# Sheet1.net
KiCad netlist of a schematic drawn in Altium Designer
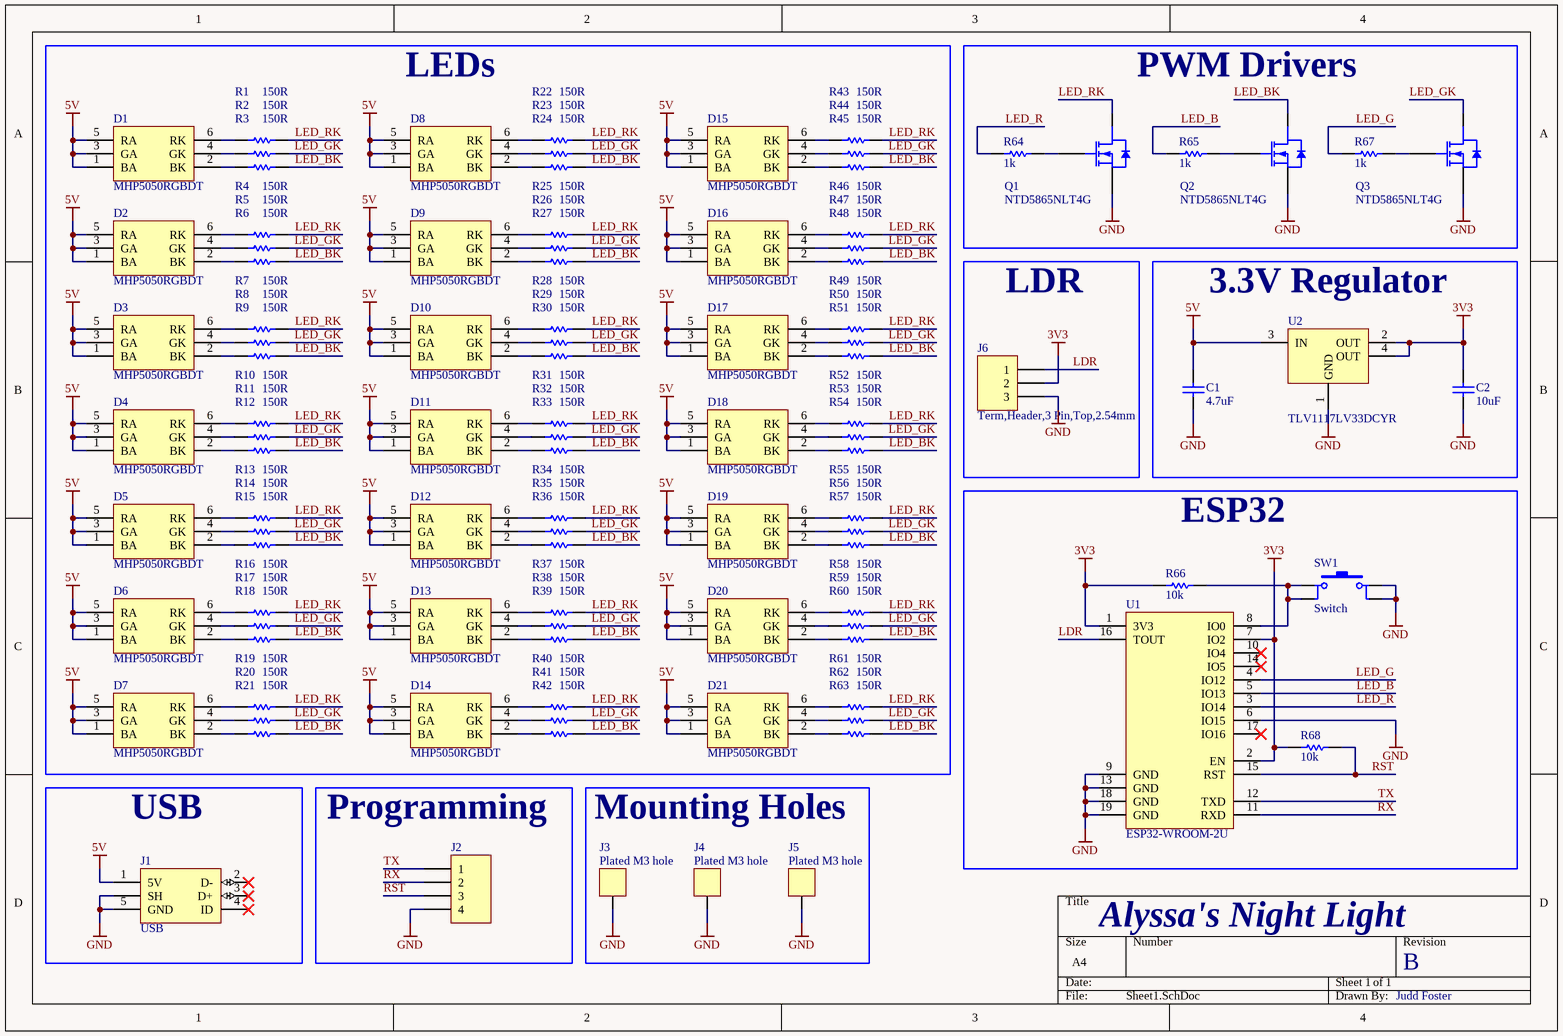
[diagram p0: Sheet1.SchDoc]

(export (version "E")
  (design (tool "Eeschema 10.0.6"))
  (components
    (comp (ref "C1")
      (value "4.7uF")
      (footprint "Cap,SMD,0805")
      (description "4.7µF ±10% 16V Ceramic Capacitor X7R 0805 (2012 Metric)")
      (fields
        (field (name "VENDOR PART NUMBER") "490-14466-1-ND")
        (field (name "MANUFACTURER") "KEMET")
        (field (name "CREATEDBY") "Judd Foster")
      )
      (libsource (lib "symbols") (part "CAP,Cer,4.7uF,16VDC,X7R,0805"))
    )
    (comp (ref "C2")
      (value "10uF")
      (footprint "Cap,SMD,0805")
      (description "CAP CER 10UF 10V X5R 0805")
      (fields
        (field (name "VENDOR PART NUMBER") "399-4925-1-ND")
        (field (name "MANUFACTURER") "KEMET")
        (field (name "CREATEDBY") "Judd Foster")
      )
      (libsource (lib "symbols") (part "CAP,Cer,10uF,10VDC,X5R,0805"))
    )
    (comp (ref "D1")
      (value "MHP5050RGBDT")
      (footprint "LED,RGB,SMD,5050")
      (description "SMD,5x5mm Light Emitting Diodes (LED) RoHS")
      (fields
        (field (name "MANUFACTURER") "MEIHUA")
        (field (name "VENDOR PART NUMBER") "C409780")
        (field (name "CREATEDBY") "Judd Foster")
      )
      (libsource (lib "symbols") (part "LED,Tri-Color,RGB,SMD,5050"))
    )
    (comp (ref "D2")
      (value "MHP5050RGBDT")
      (footprint "LED,RGB,SMD,5050")
      (description "SMD,5x5mm Light Emitting Diodes (LED) RoHS")
      (fields
        (field (name "MANUFACTURER") "MEIHUA")
        (field (name "VENDOR PART NUMBER") "C409780")
        (field (name "CREATEDBY") "Judd Foster")
      )
      (libsource (lib "symbols") (part "LED,Tri-Color,RGB,SMD,5050"))
    )
    (comp (ref "D3")
      (value "MHP5050RGBDT")
      (footprint "LED,RGB,SMD,5050")
      (description "SMD,5x5mm Light Emitting Diodes (LED) RoHS")
      (fields
        (field (name "MANUFACTURER") "MEIHUA")
        (field (name "VENDOR PART NUMBER") "C409780")
        (field (name "CREATEDBY") "Judd Foster")
      )
      (libsource (lib "symbols") (part "LED,Tri-Color,RGB,SMD,5050"))
    )
    (comp (ref "D4")
      (value "MHP5050RGBDT")
      (footprint "LED,RGB,SMD,5050")
      (description "SMD,5x5mm Light Emitting Diodes (LED) RoHS")
      (fields
        (field (name "MANUFACTURER") "MEIHUA")
        (field (name "VENDOR PART NUMBER") "C409780")
        (field (name "CREATEDBY") "Judd Foster")
      )
      (libsource (lib "symbols") (part "LED,Tri-Color,RGB,SMD,5050"))
    )
    (comp (ref "D5")
      (value "MHP5050RGBDT")
      (footprint "LED,RGB,SMD,5050")
      (description "SMD,5x5mm Light Emitting Diodes (LED) RoHS")
      (fields
        (field (name "MANUFACTURER") "MEIHUA")
        (field (name "VENDOR PART NUMBER") "C409780")
        (field (name "CREATEDBY") "Judd Foster")
      )
      (libsource (lib "symbols") (part "LED,Tri-Color,RGB,SMD,5050"))
    )
    (comp (ref "D6")
      (value "MHP5050RGBDT")
      (footprint "LED,RGB,SMD,5050")
      (description "SMD,5x5mm Light Emitting Diodes (LED) RoHS")
      (fields
        (field (name "MANUFACTURER") "MEIHUA")
        (field (name "VENDOR PART NUMBER") "C409780")
        (field (name "CREATEDBY") "Judd Foster")
      )
      (libsource (lib "symbols") (part "LED,Tri-Color,RGB,SMD,5050"))
    )
    (comp (ref "D7")
      (value "MHP5050RGBDT")
      (footprint "LED,RGB,SMD,5050")
      (description "SMD,5x5mm Light Emitting Diodes (LED) RoHS")
      (fields
        (field (name "MANUFACTURER") "MEIHUA")
        (field (name "VENDOR PART NUMBER") "C409780")
        (field (name "CREATEDBY") "Judd Foster")
      )
      (libsource (lib "symbols") (part "LED,Tri-Color,RGB,SMD,5050"))
    )
    (comp (ref "D8")
      (value "MHP5050RGBDT")
      (footprint "LED,RGB,SMD,5050")
      (description "SMD,5x5mm Light Emitting Diodes (LED) RoHS")
      (fields
        (field (name "MANUFACTURER") "MEIHUA")
        (field (name "VENDOR PART NUMBER") "C409780")
        (field (name "CREATEDBY") "Judd Foster")
      )
      (libsource (lib "symbols") (part "LED,Tri-Color,RGB,SMD,5050"))
    )
    (comp (ref "D9")
      (value "MHP5050RGBDT")
      (footprint "LED,RGB,SMD,5050")
      (description "SMD,5x5mm Light Emitting Diodes (LED) RoHS")
      (fields
        (field (name "MANUFACTURER") "MEIHUA")
        (field (name "VENDOR PART NUMBER") "C409780")
        (field (name "CREATEDBY") "Judd Foster")
      )
      (libsource (lib "symbols") (part "LED,Tri-Color,RGB,SMD,5050"))
    )
    (comp (ref "D10")
      (value "MHP5050RGBDT")
      (footprint "LED,RGB,SMD,5050")
      (description "SMD,5x5mm Light Emitting Diodes (LED) RoHS")
      (fields
        (field (name "MANUFACTURER") "MEIHUA")
        (field (name "VENDOR PART NUMBER") "C409780")
        (field (name "CREATEDBY") "Judd Foster")
      )
      (libsource (lib "symbols") (part "LED,Tri-Color,RGB,SMD,5050"))
    )
    (comp (ref "D11")
      (value "MHP5050RGBDT")
      (footprint "LED,RGB,SMD,5050")
      (description "SMD,5x5mm Light Emitting Diodes (LED) RoHS")
      (fields
        (field (name "MANUFACTURER") "MEIHUA")
        (field (name "VENDOR PART NUMBER") "C409780")
        (field (name "CREATEDBY") "Judd Foster")
      )
      (libsource (lib "symbols") (part "LED,Tri-Color,RGB,SMD,5050"))
    )
    (comp (ref "D12")
      (value "MHP5050RGBDT")
      (footprint "LED,RGB,SMD,5050")
      (description "SMD,5x5mm Light Emitting Diodes (LED) RoHS")
      (fields
        (field (name "MANUFACTURER") "MEIHUA")
        (field (name "VENDOR PART NUMBER") "C409780")
        (field (name "CREATEDBY") "Judd Foster")
      )
      (libsource (lib "symbols") (part "LED,Tri-Color,RGB,SMD,5050"))
    )
    (comp (ref "D13")
      (value "MHP5050RGBDT")
      (footprint "LED,RGB,SMD,5050")
      (description "SMD,5x5mm Light Emitting Diodes (LED) RoHS")
      (fields
        (field (name "MANUFACTURER") "MEIHUA")
        (field (name "VENDOR PART NUMBER") "C409780")
        (field (name "CREATEDBY") "Judd Foster")
      )
      (libsource (lib "symbols") (part "LED,Tri-Color,RGB,SMD,5050"))
    )
    (comp (ref "D14")
      (value "MHP5050RGBDT")
      (footprint "LED,RGB,SMD,5050")
      (description "SMD,5x5mm Light Emitting Diodes (LED) RoHS")
      (fields
        (field (name "MANUFACTURER") "MEIHUA")
        (field (name "VENDOR PART NUMBER") "C409780")
        (field (name "CREATEDBY") "Judd Foster")
      )
      (libsource (lib "symbols") (part "LED,Tri-Color,RGB,SMD,5050"))
    )
    (comp (ref "D15")
      (value "MHP5050RGBDT")
      (footprint "LED,RGB,SMD,5050")
      (description "SMD,5x5mm Light Emitting Diodes (LED) RoHS")
      (fields
        (field (name "MANUFACTURER") "MEIHUA")
        (field (name "VENDOR PART NUMBER") "C409780")
        (field (name "CREATEDBY") "Judd Foster")
      )
      (libsource (lib "symbols") (part "LED,Tri-Color,RGB,SMD,5050"))
    )
    (comp (ref "D16")
      (value "MHP5050RGBDT")
      (footprint "LED,RGB,SMD,5050")
      (description "SMD,5x5mm Light Emitting Diodes (LED) RoHS")
      (fields
        (field (name "MANUFACTURER") "MEIHUA")
        (field (name "VENDOR PART NUMBER") "C409780")
        (field (name "CREATEDBY") "Judd Foster")
      )
      (libsource (lib "symbols") (part "LED,Tri-Color,RGB,SMD,5050"))
    )
    (comp (ref "D17")
      (value "MHP5050RGBDT")
      (footprint "LED,RGB,SMD,5050")
      (description "SMD,5x5mm Light Emitting Diodes (LED) RoHS")
      (fields
        (field (name "MANUFACTURER") "MEIHUA")
        (field (name "VENDOR PART NUMBER") "C409780")
        (field (name "CREATEDBY") "Judd Foster")
      )
      (libsource (lib "symbols") (part "LED,Tri-Color,RGB,SMD,5050"))
    )
    (comp (ref "D18")
      (value "MHP5050RGBDT")
      (footprint "LED,RGB,SMD,5050")
      (description "SMD,5x5mm Light Emitting Diodes (LED) RoHS")
      (fields
        (field (name "MANUFACTURER") "MEIHUA")
        (field (name "VENDOR PART NUMBER") "C409780")
        (field (name "CREATEDBY") "Judd Foster")
      )
      (libsource (lib "symbols") (part "LED,Tri-Color,RGB,SMD,5050"))
    )
    (comp (ref "D19")
      (value "MHP5050RGBDT")
      (footprint "LED,RGB,SMD,5050")
      (description "SMD,5x5mm Light Emitting Diodes (LED) RoHS")
      (fields
        (field (name "MANUFACTURER") "MEIHUA")
        (field (name "VENDOR PART NUMBER") "C409780")
        (field (name "CREATEDBY") "Judd Foster")
      )
      (libsource (lib "symbols") (part "LED,Tri-Color,RGB,SMD,5050"))
    )
    (comp (ref "D20")
      (value "MHP5050RGBDT")
      (footprint "LED,RGB,SMD,5050")
      (description "SMD,5x5mm Light Emitting Diodes (LED) RoHS")
      (fields
        (field (name "MANUFACTURER") "MEIHUA")
        (field (name "VENDOR PART NUMBER") "C409780")
        (field (name "CREATEDBY") "Judd Foster")
      )
      (libsource (lib "symbols") (part "LED,Tri-Color,RGB,SMD,5050"))
    )
    (comp (ref "D21")
      (value "MHP5050RGBDT")
      (footprint "LED,RGB,SMD,5050")
      (description "SMD,5x5mm Light Emitting Diodes (LED) RoHS")
      (fields
        (field (name "MANUFACTURER") "MEIHUA")
        (field (name "VENDOR PART NUMBER") "C409780")
        (field (name "CREATEDBY") "Judd Foster")
      )
      (libsource (lib "symbols") (part "LED,Tri-Color,RGB,SMD,5050"))
    )
    (comp (ref "J1")
      (value "USB")
      (footprint "Conn,USB,MicroB,SMD")
      (description "USB - micro B USB 2.0 Receptacle Connector 5 Position Surface Mount, Right Angle; Through Hole")
      (fields
        (field (name "MANUFACTURER") "Amphenol ICC (FCI)")
        (field (name "MANUFACTURER PART NUMBER") "10118193-0001LF")
        (field (name "CREATEDBY") "Judd Foster")
      )
      (libsource (lib "symbols") (part "Conn,USB.Micro_B,SMD"))
    )
    (comp (ref "J2")
      (value "Term,Header,4 Pin,Top,2.54mm")
      (footprint "Term,Header,4Pin,2.54mm")
      (description "Connector Header Through Hole 4 position 0.100\" (2.54mm)")
      (fields
        (field (name "VENDOR PART NUMBER") "609-10082627-404HLF-ND")
        (field (name "MANUFACTURER") "Amphenol ICC (FCI)")
        (field (name "CREATED BY") "Judd Foster")
      )
      (libsource (lib "symbols") (part "Term,Header,4 Pin,Top,2.54mm"))
    )
    (comp (ref "J3")
      (value "Plated M3 hole")
      (footprint "HOLE,M3,3mm,PLATED")
      (description "3.5mm Drill, 7.4mm Pad, PTH")
      (fields (field (name "CREATEDBY") "Judd Foster"))
      (libsource (lib "symbols") (part "Mech,Hole,M3,3mm,Plated"))
    )
    (comp (ref "J4")
      (value "Plated M3 hole")
      (footprint "HOLE,M3,3mm,PLATED")
      (description "3.5mm Drill, 7.4mm Pad, PTH")
      (fields (field (name "CREATEDBY") "Judd Foster"))
      (libsource (lib "symbols") (part "Mech,Hole,M3,3mm,Plated"))
    )
    (comp (ref "J5")
      (value "Plated M3 hole")
      (footprint "HOLE,M3,3mm,PLATED")
      (description "3.5mm Drill, 7.4mm Pad, PTH")
      (fields (field (name "CREATEDBY") "Judd Foster"))
      (libsource (lib "symbols") (part "Mech,Hole,M3,3mm,Plated"))
    )
    (comp (ref "J6")
      (value "Term,Header,3 Pin,Top,2.54mm")
      (footprint "Term,Header,3Pin,2.54mm")
      (description "CONN HEADER VERT 3POS 2.54MM")
      (fields
        (field (name "VENDOR PART NUMBER") "732-5316-ND")
        (field (name "MANUFACTURER") "Würth Elektronik")
        (field (name "CREATED BY") "Judd Foster")
      )
      (libsource (lib "symbols") (part "Term,Header,3 Pin,Top,2.54mm"))
    )
    (comp (ref "Q1")
      (value "NTD5865NLT4G")
      (footprint "DPAK3 (TO-252 3 Lead)")
      (description "MOSFET N-CH 60V 46A DPAK")
      (fields
        (field (name "MANUFACTURER") "ON Semiconductor")
        (field (name "VENDOR PART NUMBER") "NTD5865NLT4GOSCT-ND")
        (field (name "CREATEDBY") "Judd Foster")
      )
      (libsource (lib "symbols") (part "MOSFET,N Ch,60V,46A"))
    )
    (comp (ref "Q2")
      (value "NTD5865NLT4G")
      (footprint "DPAK3 (TO-252 3 Lead)")
      (description "MOSFET N-CH 60V 46A DPAK")
      (fields
        (field (name "MANUFACTURER") "ON Semiconductor")
        (field (name "VENDOR PART NUMBER") "NTD5865NLT4GOSCT-ND")
        (field (name "CREATEDBY") "Judd Foster")
      )
      (libsource (lib "symbols") (part "MOSFET,N Ch,60V,46A"))
    )
    (comp (ref "Q3")
      (value "NTD5865NLT4G")
      (footprint "DPAK3 (TO-252 3 Lead)")
      (description "MOSFET N-CH 60V 46A DPAK")
      (fields
        (field (name "MANUFACTURER") "ON Semiconductor")
        (field (name "VENDOR PART NUMBER") "NTD5865NLT4GOSCT-ND")
        (field (name "CREATEDBY") "Judd Foster")
      )
      (libsource (lib "symbols") (part "MOSFET,N Ch,60V,46A"))
    )
    (comp (ref "R1")
      (value "150R")
      (footprint "RES,0603")
      (fields
        (field (name "MANUFACTURER") "TE Connectivity Passive Product")
        (field (name "MANUFACTURER PART NUMBER") "CRGCQ0603F150R")
        (field (name "VENDOR PART NUMBER") "A129678CT-ND")
        (field (name "CREATEDBY") "Judd Foster")
      )
      (libsource (lib "symbols") (part "RES,150R,1%,0.1W,0603"))
    )
    (comp (ref "R2")
      (value "150R")
      (footprint "RES,0603")
      (fields
        (field (name "MANUFACTURER") "TE Connectivity Passive Product")
        (field (name "MANUFACTURER PART NUMBER") "CRGCQ0603F150R")
        (field (name "VENDOR PART NUMBER") "A129678CT-ND")
        (field (name "CREATEDBY") "Judd Foster")
      )
      (libsource (lib "symbols") (part "RES,150R,1%,0.1W,0603"))
    )
    (comp (ref "R3")
      (value "150R")
      (footprint "RES,0603")
      (fields
        (field (name "MANUFACTURER") "TE Connectivity Passive Product")
        (field (name "MANUFACTURER PART NUMBER") "CRGCQ0603F150R")
        (field (name "VENDOR PART NUMBER") "A129678CT-ND")
        (field (name "CREATEDBY") "Judd Foster")
      )
      (libsource (lib "symbols") (part "RES,150R,1%,0.1W,0603"))
    )
    (comp (ref "R4")
      (value "150R")
      (footprint "RES,0603")
      (fields
        (field (name "MANUFACTURER") "TE Connectivity Passive Product")
        (field (name "MANUFACTURER PART NUMBER") "CRGCQ0603F150R")
        (field (name "VENDOR PART NUMBER") "A129678CT-ND")
        (field (name "CREATEDBY") "Judd Foster")
      )
      (libsource (lib "symbols") (part "RES,150R,1%,0.1W,0603"))
    )
    (comp (ref "R5")
      (value "150R")
      (footprint "RES,0603")
      (fields
        (field (name "MANUFACTURER") "TE Connectivity Passive Product")
        (field (name "MANUFACTURER PART NUMBER") "CRGCQ0603F150R")
        (field (name "VENDOR PART NUMBER") "A129678CT-ND")
        (field (name "CREATEDBY") "Judd Foster")
      )
      (libsource (lib "symbols") (part "RES,150R,1%,0.1W,0603"))
    )
    (comp (ref "R6")
      (value "150R")
      (footprint "RES,0603")
      (fields
        (field (name "MANUFACTURER") "TE Connectivity Passive Product")
        (field (name "MANUFACTURER PART NUMBER") "CRGCQ0603F150R")
        (field (name "VENDOR PART NUMBER") "A129678CT-ND")
        (field (name "CREATEDBY") "Judd Foster")
      )
      (libsource (lib "symbols") (part "RES,150R,1%,0.1W,0603"))
    )
    (comp (ref "R7")
      (value "150R")
      (footprint "RES,0603")
      (fields
        (field (name "MANUFACTURER") "TE Connectivity Passive Product")
        (field (name "MANUFACTURER PART NUMBER") "CRGCQ0603F150R")
        (field (name "VENDOR PART NUMBER") "A129678CT-ND")
        (field (name "CREATEDBY") "Judd Foster")
      )
      (libsource (lib "symbols") (part "RES,150R,1%,0.1W,0603"))
    )
    (comp (ref "R8")
      (value "150R")
      (footprint "RES,0603")
      (fields
        (field (name "MANUFACTURER") "TE Connectivity Passive Product")
        (field (name "MANUFACTURER PART NUMBER") "CRGCQ0603F150R")
        (field (name "VENDOR PART NUMBER") "A129678CT-ND")
        (field (name "CREATEDBY") "Judd Foster")
      )
      (libsource (lib "symbols") (part "RES,150R,1%,0.1W,0603"))
    )
    (comp (ref "R9")
      (value "150R")
      (footprint "RES,0603")
      (fields
        (field (name "MANUFACTURER") "TE Connectivity Passive Product")
        (field (name "MANUFACTURER PART NUMBER") "CRGCQ0603F150R")
        (field (name "VENDOR PART NUMBER") "A129678CT-ND")
        (field (name "CREATEDBY") "Judd Foster")
      )
      (libsource (lib "symbols") (part "RES,150R,1%,0.1W,0603"))
    )
    (comp (ref "R10")
      (value "150R")
      (footprint "RES,0603")
      (fields
        (field (name "MANUFACTURER") "TE Connectivity Passive Product")
        (field (name "MANUFACTURER PART NUMBER") "CRGCQ0603F150R")
        (field (name "VENDOR PART NUMBER") "A129678CT-ND")
        (field (name "CREATEDBY") "Judd Foster")
      )
      (libsource (lib "symbols") (part "RES,150R,1%,0.1W,0603"))
    )
    (comp (ref "R11")
      (value "150R")
      (footprint "RES,0603")
      (fields
        (field (name "MANUFACTURER") "TE Connectivity Passive Product")
        (field (name "MANUFACTURER PART NUMBER") "CRGCQ0603F150R")
        (field (name "VENDOR PART NUMBER") "A129678CT-ND")
        (field (name "CREATEDBY") "Judd Foster")
      )
      (libsource (lib "symbols") (part "RES,150R,1%,0.1W,0603"))
    )
    (comp (ref "R12")
      (value "150R")
      (footprint "RES,0603")
      (fields
        (field (name "MANUFACTURER") "TE Connectivity Passive Product")
        (field (name "MANUFACTURER PART NUMBER") "CRGCQ0603F150R")
        (field (name "VENDOR PART NUMBER") "A129678CT-ND")
        (field (name "CREATEDBY") "Judd Foster")
      )
      (libsource (lib "symbols") (part "RES,150R,1%,0.1W,0603"))
    )
    (comp (ref "R13")
      (value "150R")
      (footprint "RES,0603")
      (fields
        (field (name "MANUFACTURER") "TE Connectivity Passive Product")
        (field (name "MANUFACTURER PART NUMBER") "CRGCQ0603F150R")
        (field (name "VENDOR PART NUMBER") "A129678CT-ND")
        (field (name "CREATEDBY") "Judd Foster")
      )
      (libsource (lib "symbols") (part "RES,150R,1%,0.1W,0603"))
    )
    (comp (ref "R14")
      (value "150R")
      (footprint "RES,0603")
      (fields
        (field (name "MANUFACTURER") "TE Connectivity Passive Product")
        (field (name "MANUFACTURER PART NUMBER") "CRGCQ0603F150R")
        (field (name "VENDOR PART NUMBER") "A129678CT-ND")
        (field (name "CREATEDBY") "Judd Foster")
      )
      (libsource (lib "symbols") (part "RES,150R,1%,0.1W,0603"))
    )
    (comp (ref "R15")
      (value "150R")
      (footprint "RES,0603")
      (fields
        (field (name "MANUFACTURER") "TE Connectivity Passive Product")
        (field (name "MANUFACTURER PART NUMBER") "CRGCQ0603F150R")
        (field (name "VENDOR PART NUMBER") "A129678CT-ND")
        (field (name "CREATEDBY") "Judd Foster")
      )
      (libsource (lib "symbols") (part "RES,150R,1%,0.1W,0603"))
    )
    (comp (ref "R16")
      (value "150R")
      (footprint "RES,0603")
      (fields
        (field (name "MANUFACTURER") "TE Connectivity Passive Product")
        (field (name "MANUFACTURER PART NUMBER") "CRGCQ0603F150R")
        (field (name "VENDOR PART NUMBER") "A129678CT-ND")
        (field (name "CREATEDBY") "Judd Foster")
      )
      (libsource (lib "symbols") (part "RES,150R,1%,0.1W,0603"))
    )
    (comp (ref "R17")
      (value "150R")
      (footprint "RES,0603")
      (fields
        (field (name "MANUFACTURER") "TE Connectivity Passive Product")
        (field (name "MANUFACTURER PART NUMBER") "CRGCQ0603F150R")
        (field (name "VENDOR PART NUMBER") "A129678CT-ND")
        (field (name "CREATEDBY") "Judd Foster")
      )
      (libsource (lib "symbols") (part "RES,150R,1%,0.1W,0603"))
    )
    (comp (ref "R18")
      (value "150R")
      (footprint "RES,0603")
      (fields
        (field (name "MANUFACTURER") "TE Connectivity Passive Product")
        (field (name "MANUFACTURER PART NUMBER") "CRGCQ0603F150R")
        (field (name "VENDOR PART NUMBER") "A129678CT-ND")
        (field (name "CREATEDBY") "Judd Foster")
      )
      (libsource (lib "symbols") (part "RES,150R,1%,0.1W,0603"))
    )
    (comp (ref "R19")
      (value "150R")
      (footprint "RES,0603")
      (fields
        (field (name "MANUFACTURER") "TE Connectivity Passive Product")
        (field (name "MANUFACTURER PART NUMBER") "CRGCQ0603F150R")
        (field (name "VENDOR PART NUMBER") "A129678CT-ND")
        (field (name "CREATEDBY") "Judd Foster")
      )
      (libsource (lib "symbols") (part "RES,150R,1%,0.1W,0603"))
    )
    (comp (ref "R20")
      (value "150R")
      (footprint "RES,0603")
      (fields
        (field (name "MANUFACTURER") "TE Connectivity Passive Product")
        (field (name "MANUFACTURER PART NUMBER") "CRGCQ0603F150R")
        (field (name "VENDOR PART NUMBER") "A129678CT-ND")
        (field (name "CREATEDBY") "Judd Foster")
      )
      (libsource (lib "symbols") (part "RES,150R,1%,0.1W,0603"))
    )
    (comp (ref "R21")
      (value "150R")
      (footprint "RES,0603")
      (fields
        (field (name "MANUFACTURER") "TE Connectivity Passive Product")
        (field (name "MANUFACTURER PART NUMBER") "CRGCQ0603F150R")
        (field (name "VENDOR PART NUMBER") "A129678CT-ND")
        (field (name "CREATEDBY") "Judd Foster")
      )
      (libsource (lib "symbols") (part "RES,150R,1%,0.1W,0603"))
    )
    (comp (ref "R22")
      (value "150R")
      (footprint "RES,0603")
      (fields
        (field (name "MANUFACTURER") "TE Connectivity Passive Product")
        (field (name "MANUFACTURER PART NUMBER") "CRGCQ0603F150R")
        (field (name "VENDOR PART NUMBER") "A129678CT-ND")
        (field (name "CREATEDBY") "Judd Foster")
      )
      (libsource (lib "symbols") (part "RES,150R,1%,0.1W,0603"))
    )
    (comp (ref "R23")
      (value "150R")
      (footprint "RES,0603")
      (fields
        (field (name "MANUFACTURER") "TE Connectivity Passive Product")
        (field (name "MANUFACTURER PART NUMBER") "CRGCQ0603F150R")
        (field (name "VENDOR PART NUMBER") "A129678CT-ND")
        (field (name "CREATEDBY") "Judd Foster")
      )
      (libsource (lib "symbols") (part "RES,150R,1%,0.1W,0603"))
    )
    (comp (ref "R24")
      (value "150R")
      (footprint "RES,0603")
      (fields
        (field (name "MANUFACTURER") "TE Connectivity Passive Product")
        (field (name "MANUFACTURER PART NUMBER") "CRGCQ0603F150R")
        (field (name "VENDOR PART NUMBER") "A129678CT-ND")
        (field (name "CREATEDBY") "Judd Foster")
      )
      (libsource (lib "symbols") (part "RES,150R,1%,0.1W,0603"))
    )
    (comp (ref "R25")
      (value "150R")
      (footprint "RES,0603")
      (fields
        (field (name "MANUFACTURER") "TE Connectivity Passive Product")
        (field (name "MANUFACTURER PART NUMBER") "CRGCQ0603F150R")
        (field (name "VENDOR PART NUMBER") "A129678CT-ND")
        (field (name "CREATEDBY") "Judd Foster")
      )
      (libsource (lib "symbols") (part "RES,150R,1%,0.1W,0603"))
    )
    (comp (ref "R26")
      (value "150R")
      (footprint "RES,0603")
      (fields
        (field (name "MANUFACTURER") "TE Connectivity Passive Product")
        (field (name "MANUFACTURER PART NUMBER") "CRGCQ0603F150R")
        (field (name "VENDOR PART NUMBER") "A129678CT-ND")
        (field (name "CREATEDBY") "Judd Foster")
      )
      (libsource (lib "symbols") (part "RES,150R,1%,0.1W,0603"))
    )
    (comp (ref "R27")
      (value "150R")
      (footprint "RES,0603")
      (fields
        (field (name "MANUFACTURER") "TE Connectivity Passive Product")
        (field (name "MANUFACTURER PART NUMBER") "CRGCQ0603F150R")
        (field (name "VENDOR PART NUMBER") "A129678CT-ND")
        (field (name "CREATEDBY") "Judd Foster")
      )
      (libsource (lib "symbols") (part "RES,150R,1%,0.1W,0603"))
    )
    (comp (ref "R28")
      (value "150R")
      (footprint "RES,0603")
      (fields
        (field (name "MANUFACTURER") "TE Connectivity Passive Product")
        (field (name "MANUFACTURER PART NUMBER") "CRGCQ0603F150R")
        (field (name "VENDOR PART NUMBER") "A129678CT-ND")
        (field (name "CREATEDBY") "Judd Foster")
      )
      (libsource (lib "symbols") (part "RES,150R,1%,0.1W,0603"))
    )
    (comp (ref "R29")
      (value "150R")
      (footprint "RES,0603")
      (fields
        (field (name "MANUFACTURER") "TE Connectivity Passive Product")
        (field (name "MANUFACTURER PART NUMBER") "CRGCQ0603F150R")
        (field (name "VENDOR PART NUMBER") "A129678CT-ND")
        (field (name "CREATEDBY") "Judd Foster")
      )
      (libsource (lib "symbols") (part "RES,150R,1%,0.1W,0603"))
    )
    (comp (ref "R30")
      (value "150R")
      (footprint "RES,0603")
      (fields
        (field (name "MANUFACTURER") "TE Connectivity Passive Product")
        (field (name "MANUFACTURER PART NUMBER") "CRGCQ0603F150R")
        (field (name "VENDOR PART NUMBER") "A129678CT-ND")
        (field (name "CREATEDBY") "Judd Foster")
      )
      (libsource (lib "symbols") (part "RES,150R,1%,0.1W,0603"))
    )
    (comp (ref "R31")
      (value "150R")
      (footprint "RES,0603")
      (fields
        (field (name "MANUFACTURER") "TE Connectivity Passive Product")
        (field (name "MANUFACTURER PART NUMBER") "CRGCQ0603F150R")
        (field (name "VENDOR PART NUMBER") "A129678CT-ND")
        (field (name "CREATEDBY") "Judd Foster")
      )
      (libsource (lib "symbols") (part "RES,150R,1%,0.1W,0603"))
    )
    (comp (ref "R32")
      (value "150R")
      (footprint "RES,0603")
      (fields
        (field (name "MANUFACTURER") "TE Connectivity Passive Product")
        (field (name "MANUFACTURER PART NUMBER") "CRGCQ0603F150R")
        (field (name "VENDOR PART NUMBER") "A129678CT-ND")
        (field (name "CREATEDBY") "Judd Foster")
      )
      (libsource (lib "symbols") (part "RES,150R,1%,0.1W,0603"))
    )
    (comp (ref "R33")
      (value "150R")
      (footprint "RES,0603")
      (fields
        (field (name "MANUFACTURER") "TE Connectivity Passive Product")
        (field (name "MANUFACTURER PART NUMBER") "CRGCQ0603F150R")
        (field (name "VENDOR PART NUMBER") "A129678CT-ND")
        (field (name "CREATEDBY") "Judd Foster")
      )
      (libsource (lib "symbols") (part "RES,150R,1%,0.1W,0603"))
    )
    (comp (ref "R34")
      (value "150R")
      (footprint "RES,0603")
      (fields
        (field (name "MANUFACTURER") "TE Connectivity Passive Product")
        (field (name "MANUFACTURER PART NUMBER") "CRGCQ0603F150R")
        (field (name "VENDOR PART NUMBER") "A129678CT-ND")
        (field (name "CREATEDBY") "Judd Foster")
      )
      (libsource (lib "symbols") (part "RES,150R,1%,0.1W,0603"))
    )
    (comp (ref "R35")
      (value "150R")
      (footprint "RES,0603")
      (fields
        (field (name "MANUFACTURER") "TE Connectivity Passive Product")
        (field (name "MANUFACTURER PART NUMBER") "CRGCQ0603F150R")
        (field (name "VENDOR PART NUMBER") "A129678CT-ND")
        (field (name "CREATEDBY") "Judd Foster")
      )
      (libsource (lib "symbols") (part "RES,150R,1%,0.1W,0603"))
    )
    (comp (ref "R36")
      (value "150R")
      (footprint "RES,0603")
      (fields
        (field (name "MANUFACTURER") "TE Connectivity Passive Product")
        (field (name "MANUFACTURER PART NUMBER") "CRGCQ0603F150R")
        (field (name "VENDOR PART NUMBER") "A129678CT-ND")
        (field (name "CREATEDBY") "Judd Foster")
      )
      (libsource (lib "symbols") (part "RES,150R,1%,0.1W,0603"))
    )
    (comp (ref "R37")
      (value "150R")
      (footprint "RES,0603")
      (fields
        (field (name "MANUFACTURER") "TE Connectivity Passive Product")
        (field (name "MANUFACTURER PART NUMBER") "CRGCQ0603F150R")
        (field (name "VENDOR PART NUMBER") "A129678CT-ND")
        (field (name "CREATEDBY") "Judd Foster")
      )
      (libsource (lib "symbols") (part "RES,150R,1%,0.1W,0603"))
    )
    (comp (ref "R38")
      (value "150R")
      (footprint "RES,0603")
      (fields
        (field (name "MANUFACTURER") "TE Connectivity Passive Product")
        (field (name "MANUFACTURER PART NUMBER") "CRGCQ0603F150R")
        (field (name "VENDOR PART NUMBER") "A129678CT-ND")
        (field (name "CREATEDBY") "Judd Foster")
      )
      (libsource (lib "symbols") (part "RES,150R,1%,0.1W,0603"))
    )
    (comp (ref "R39")
      (value "150R")
      (footprint "RES,0603")
      (fields
        (field (name "MANUFACTURER") "TE Connectivity Passive Product")
        (field (name "MANUFACTURER PART NUMBER") "CRGCQ0603F150R")
        (field (name "VENDOR PART NUMBER") "A129678CT-ND")
        (field (name "CREATEDBY") "Judd Foster")
      )
      (libsource (lib "symbols") (part "RES,150R,1%,0.1W,0603"))
    )
    (comp (ref "R40")
      (value "150R")
      (footprint "RES,0603")
      (fields
        (field (name "MANUFACTURER") "TE Connectivity Passive Product")
        (field (name "MANUFACTURER PART NUMBER") "CRGCQ0603F150R")
        (field (name "VENDOR PART NUMBER") "A129678CT-ND")
        (field (name "CREATEDBY") "Judd Foster")
      )
      (libsource (lib "symbols") (part "RES,150R,1%,0.1W,0603"))
    )
    (comp (ref "R41")
      (value "150R")
      (footprint "RES,0603")
      (fields
        (field (name "MANUFACTURER") "TE Connectivity Passive Product")
        (field (name "MANUFACTURER PART NUMBER") "CRGCQ0603F150R")
        (field (name "VENDOR PART NUMBER") "A129678CT-ND")
        (field (name "CREATEDBY") "Judd Foster")
      )
      (libsource (lib "symbols") (part "RES,150R,1%,0.1W,0603"))
    )
    (comp (ref "R42")
      (value "150R")
      (footprint "RES,0603")
      (fields
        (field (name "MANUFACTURER") "TE Connectivity Passive Product")
        (field (name "MANUFACTURER PART NUMBER") "CRGCQ0603F150R")
        (field (name "VENDOR PART NUMBER") "A129678CT-ND")
        (field (name "CREATEDBY") "Judd Foster")
      )
      (libsource (lib "symbols") (part "RES,150R,1%,0.1W,0603"))
    )
    (comp (ref "R43")
      (value "150R")
      (footprint "RES,0603")
      (fields
        (field (name "MANUFACTURER") "TE Connectivity Passive Product")
        (field (name "MANUFACTURER PART NUMBER") "CRGCQ0603F150R")
        (field (name "VENDOR PART NUMBER") "A129678CT-ND")
        (field (name "CREATEDBY") "Judd Foster")
      )
      (libsource (lib "symbols") (part "RES,150R,1%,0.1W,0603"))
    )
    (comp (ref "R44")
      (value "150R")
      (footprint "RES,0603")
      (fields
        (field (name "MANUFACTURER") "TE Connectivity Passive Product")
        (field (name "MANUFACTURER PART NUMBER") "CRGCQ0603F150R")
        (field (name "VENDOR PART NUMBER") "A129678CT-ND")
        (field (name "CREATEDBY") "Judd Foster")
      )
      (libsource (lib "symbols") (part "RES,150R,1%,0.1W,0603"))
    )
    (comp (ref "R45")
      (value "150R")
      (footprint "RES,0603")
      (fields
        (field (name "MANUFACTURER") "TE Connectivity Passive Product")
        (field (name "MANUFACTURER PART NUMBER") "CRGCQ0603F150R")
        (field (name "VENDOR PART NUMBER") "A129678CT-ND")
        (field (name "CREATEDBY") "Judd Foster")
      )
      (libsource (lib "symbols") (part "RES,150R,1%,0.1W,0603"))
    )
    (comp (ref "R46")
      (value "150R")
      (footprint "RES,0603")
      (fields
        (field (name "MANUFACTURER") "TE Connectivity Passive Product")
        (field (name "MANUFACTURER PART NUMBER") "CRGCQ0603F150R")
        (field (name "VENDOR PART NUMBER") "A129678CT-ND")
        (field (name "CREATEDBY") "Judd Foster")
      )
      (libsource (lib "symbols") (part "RES,150R,1%,0.1W,0603"))
    )
    (comp (ref "R47")
      (value "150R")
      (footprint "RES,0603")
      (fields
        (field (name "MANUFACTURER") "TE Connectivity Passive Product")
        (field (name "MANUFACTURER PART NUMBER") "CRGCQ0603F150R")
        (field (name "VENDOR PART NUMBER") "A129678CT-ND")
        (field (name "CREATEDBY") "Judd Foster")
      )
      (libsource (lib "symbols") (part "RES,150R,1%,0.1W,0603"))
    )
    (comp (ref "R48")
      (value "150R")
      (footprint "RES,0603")
      (fields
        (field (name "MANUFACTURER") "TE Connectivity Passive Product")
        (field (name "MANUFACTURER PART NUMBER") "CRGCQ0603F150R")
        (field (name "VENDOR PART NUMBER") "A129678CT-ND")
        (field (name "CREATEDBY") "Judd Foster")
      )
      (libsource (lib "symbols") (part "RES,150R,1%,0.1W,0603"))
    )
    (comp (ref "R49")
      (value "150R")
      (footprint "RES,0603")
      (fields
        (field (name "MANUFACTURER") "TE Connectivity Passive Product")
        (field (name "MANUFACTURER PART NUMBER") "CRGCQ0603F150R")
        (field (name "VENDOR PART NUMBER") "A129678CT-ND")
        (field (name "CREATEDBY") "Judd Foster")
      )
      (libsource (lib "symbols") (part "RES,150R,1%,0.1W,0603"))
    )
    (comp (ref "R50")
      (value "150R")
      (footprint "RES,0603")
      (fields
        (field (name "MANUFACTURER") "TE Connectivity Passive Product")
        (field (name "MANUFACTURER PART NUMBER") "CRGCQ0603F150R")
        (field (name "VENDOR PART NUMBER") "A129678CT-ND")
        (field (name "CREATEDBY") "Judd Foster")
      )
      (libsource (lib "symbols") (part "RES,150R,1%,0.1W,0603"))
    )
    (comp (ref "R51")
      (value "150R")
      (footprint "RES,0603")
      (fields
        (field (name "MANUFACTURER") "TE Connectivity Passive Product")
        (field (name "MANUFACTURER PART NUMBER") "CRGCQ0603F150R")
        (field (name "VENDOR PART NUMBER") "A129678CT-ND")
        (field (name "CREATEDBY") "Judd Foster")
      )
      (libsource (lib "symbols") (part "RES,150R,1%,0.1W,0603"))
    )
    (comp (ref "R52")
      (value "150R")
      (footprint "RES,0603")
      (fields
        (field (name "MANUFACTURER") "TE Connectivity Passive Product")
        (field (name "MANUFACTURER PART NUMBER") "CRGCQ0603F150R")
        (field (name "VENDOR PART NUMBER") "A129678CT-ND")
        (field (name "CREATEDBY") "Judd Foster")
      )
      (libsource (lib "symbols") (part "RES,150R,1%,0.1W,0603"))
    )
    (comp (ref "R53")
      (value "150R")
      (footprint "RES,0603")
      (fields
        (field (name "MANUFACTURER") "TE Connectivity Passive Product")
        (field (name "MANUFACTURER PART NUMBER") "CRGCQ0603F150R")
        (field (name "VENDOR PART NUMBER") "A129678CT-ND")
        (field (name "CREATEDBY") "Judd Foster")
      )
      (libsource (lib "symbols") (part "RES,150R,1%,0.1W,0603"))
    )
    (comp (ref "R54")
      (value "150R")
      (footprint "RES,0603")
      (fields
        (field (name "MANUFACTURER") "TE Connectivity Passive Product")
        (field (name "MANUFACTURER PART NUMBER") "CRGCQ0603F150R")
        (field (name "VENDOR PART NUMBER") "A129678CT-ND")
        (field (name "CREATEDBY") "Judd Foster")
      )
      (libsource (lib "symbols") (part "RES,150R,1%,0.1W,0603"))
    )
    (comp (ref "R55")
      (value "150R")
      (footprint "RES,0603")
      (fields
        (field (name "MANUFACTURER") "TE Connectivity Passive Product")
        (field (name "MANUFACTURER PART NUMBER") "CRGCQ0603F150R")
        (field (name "VENDOR PART NUMBER") "A129678CT-ND")
        (field (name "CREATEDBY") "Judd Foster")
      )
      (libsource (lib "symbols") (part "RES,150R,1%,0.1W,0603"))
    )
    (comp (ref "R56")
      (value "150R")
      (footprint "RES,0603")
      (fields
        (field (name "MANUFACTURER") "TE Connectivity Passive Product")
        (field (name "MANUFACTURER PART NUMBER") "CRGCQ0603F150R")
        (field (name "VENDOR PART NUMBER") "A129678CT-ND")
        (field (name "CREATEDBY") "Judd Foster")
      )
      (libsource (lib "symbols") (part "RES,150R,1%,0.1W,0603"))
    )
    (comp (ref "R57")
      (value "150R")
      (footprint "RES,0603")
      (fields
        (field (name "MANUFACTURER") "TE Connectivity Passive Product")
        (field (name "MANUFACTURER PART NUMBER") "CRGCQ0603F150R")
        (field (name "VENDOR PART NUMBER") "A129678CT-ND")
        (field (name "CREATEDBY") "Judd Foster")
      )
      (libsource (lib "symbols") (part "RES,150R,1%,0.1W,0603"))
    )
    (comp (ref "R58")
      (value "150R")
      (footprint "RES,0603")
      (fields
        (field (name "MANUFACTURER") "TE Connectivity Passive Product")
        (field (name "MANUFACTURER PART NUMBER") "CRGCQ0603F150R")
        (field (name "VENDOR PART NUMBER") "A129678CT-ND")
        (field (name "CREATEDBY") "Judd Foster")
      )
      (libsource (lib "symbols") (part "RES,150R,1%,0.1W,0603"))
    )
    (comp (ref "R59")
      (value "150R")
      (footprint "RES,0603")
      (fields
        (field (name "MANUFACTURER") "TE Connectivity Passive Product")
        (field (name "MANUFACTURER PART NUMBER") "CRGCQ0603F150R")
        (field (name "VENDOR PART NUMBER") "A129678CT-ND")
        (field (name "CREATEDBY") "Judd Foster")
      )
      (libsource (lib "symbols") (part "RES,150R,1%,0.1W,0603"))
    )
    (comp (ref "R60")
      (value "150R")
      (footprint "RES,0603")
      (fields
        (field (name "MANUFACTURER") "TE Connectivity Passive Product")
        (field (name "MANUFACTURER PART NUMBER") "CRGCQ0603F150R")
        (field (name "VENDOR PART NUMBER") "A129678CT-ND")
        (field (name "CREATEDBY") "Judd Foster")
      )
      (libsource (lib "symbols") (part "RES,150R,1%,0.1W,0603"))
    )
    (comp (ref "R61")
      (value "150R")
      (footprint "RES,0603")
      (fields
        (field (name "MANUFACTURER") "TE Connectivity Passive Product")
        (field (name "MANUFACTURER PART NUMBER") "CRGCQ0603F150R")
        (field (name "VENDOR PART NUMBER") "A129678CT-ND")
        (field (name "CREATEDBY") "Judd Foster")
      )
      (libsource (lib "symbols") (part "RES,150R,1%,0.1W,0603"))
    )
    (comp (ref "R62")
      (value "150R")
      (footprint "RES,0603")
      (fields
        (field (name "MANUFACTURER") "TE Connectivity Passive Product")
        (field (name "MANUFACTURER PART NUMBER") "CRGCQ0603F150R")
        (field (name "VENDOR PART NUMBER") "A129678CT-ND")
        (field (name "CREATEDBY") "Judd Foster")
      )
      (libsource (lib "symbols") (part "RES,150R,1%,0.1W,0603"))
    )
    (comp (ref "R63")
      (value "150R")
      (footprint "RES,0603")
      (fields
        (field (name "MANUFACTURER") "TE Connectivity Passive Product")
        (field (name "MANUFACTURER PART NUMBER") "CRGCQ0603F150R")
        (field (name "VENDOR PART NUMBER") "A129678CT-ND")
        (field (name "CREATEDBY") "Judd Foster")
      )
      (libsource (lib "symbols") (part "RES,150R,1%,0.1W,0603"))
    )
    (comp (ref "R64")
      (value "1k")
      (footprint "RES,0603")
      (description "RES SMD 1K OHM 1% 1/10W 0603")
      (fields
        (field (name "MANUFACTURER") "Yageo")
        (field (name "MANUFACTURER PART NUMBER") "RC0603FR-071KL")
        (field (name "CREATEDBY") "Judd Foster")
      )
      (libsource (lib "symbols") (part "RES,1k,1%,0.1W,0603"))
    )
    (comp (ref "R65")
      (value "1k")
      (footprint "RES,0603")
      (description "RES SMD 1K OHM 1% 1/10W 0603")
      (fields
        (field (name "MANUFACTURER") "Yageo")
        (field (name "MANUFACTURER PART NUMBER") "RC0603FR-071KL")
        (field (name "CREATEDBY") "Judd Foster")
      )
      (libsource (lib "symbols") (part "RES,1k,1%,0.1W,0603"))
    )
    (comp (ref "R66")
      (value "10k")
      (footprint "RES,0603")
      (description "RES SMD 10K OHM 1% 1/10W 0603")
      (fields
        (field (name "MANUFACTURER") "Yageo")
        (field (name "MANUFACTURER PART NUMBER") "RC0603FR-0710KL")
        (field (name "CREATEDBY") "Judd Foster")
      )
      (libsource (lib "symbols") (part "RES,10k,1%,0.1W,0603"))
    )
    (comp (ref "R67")
      (value "1k")
      (footprint "RES,0603")
      (description "RES SMD 1K OHM 1% 1/10W 0603")
      (fields
        (field (name "MANUFACTURER") "Yageo")
        (field (name "MANUFACTURER PART NUMBER") "RC0603FR-071KL")
        (field (name "CREATEDBY") "Judd Foster")
      )
      (libsource (lib "symbols") (part "RES,1k,1%,0.1W,0603"))
    )
    (comp (ref "R68")
      (value "10k")
      (footprint "RES,0603")
      (description "RES SMD 10K OHM 1% 1/10W 0603")
      (fields
        (field (name "MANUFACTURER") "Yageo")
        (field (name "MANUFACTURER PART NUMBER") "RC0603FR-0710KL")
        (field (name "CREATEDBY") "Judd Foster")
      )
      (libsource (lib "symbols") (part "RES,10k,1%,0.1W,0603"))
    )
    (comp (ref "SW1")
      (value "Switch")
      (footprint "Switch,Tactile,SPST-NO,SMD")
      (description "Tactile Switch SPST-NO Top Actuated Surface Mount")
      (fields
        (field (name "MANUFACTURER") "C&K")
        (field (name "MANUFACTURER PART NUMBER") "PTS645SK43SMTR92 LFS")
        (field (name "CREATEDBY") "Judd Foster")
      )
      (libsource (lib "symbols") (part "Switch,Tactile,SPST-NO,SMD,H4.3"))
    )
    (comp (ref "U1")
      (value "ESP32-WROOM-2U")
      (footprint "ESP32-WROOM-02U")
      (description "WiFi 802.11b/g/n Transceiver Module 2.4GHz ~ 2.5GHz Integrated, Chip + IPEX Surface Mount")
      (fields
        (field (name "MANUFACTURER") "Espressif Systems")
        (field (name "MANUFACTURER PART NUMBER") "ESP-WROOM-02U (4MB)")
        (field (name "CREATEDBY") "Judd Foster")
      )
      (libsource (lib "symbols") (part "ESP32-WROOM-2U"))
    )
    (comp (ref "U2")
      (value "TLV1117LV33DCYR")
      (footprint "SOT223")
      (description "Linear Voltage Regulator IC  1 Output  1A SOT-223-4")
      (fields
        (field (name "MANUFACTURER") "Texas Instruments")
        (field (name "VENDOR PART NUMBER") "296-28778-1-ND")
        (field (name "CREATEDBY") "Judd Foster")
      )
      (libsource (lib "symbols") (part "TLV1117LV33DCYR"))
    )
  )
  (nets
    (net (code "1") (name "/LDR") (class "Default")
      (node (ref "J6") (pin "1") (pinfunction "1_1") (pintype "passive"))
      (node (ref "U1") (pin "16") (pinfunction "TOUT_16") (pintype "passive"))
    )
    (net (code "2") (name "/LED_B") (class "Default")
      (node (ref "R65") (pin "1") (pinfunction "1_1") (pintype "passive"))
      (node (ref "U1") (pin "5") (pinfunction "IO13_5") (pintype "passive"))
    )
    (net (code "3") (name "/LED_BK") (class "Default")
      (node (ref "Q2") (pin "4") (pinfunction "D_4") (pintype "passive"))
      (node (ref "R12") (pin "2") (pinfunction "2_2") (pintype "passive"))
      (node (ref "R15") (pin "2") (pinfunction "2_2") (pintype "passive"))
      (node (ref "R18") (pin "2") (pinfunction "2_2") (pintype "passive"))
      (node (ref "R21") (pin "2") (pinfunction "2_2") (pintype "passive"))
      (node (ref "R24") (pin "2") (pinfunction "2_2") (pintype "passive"))
      (node (ref "R27") (pin "2") (pinfunction "2_2") (pintype "passive"))
      (node (ref "R3") (pin "2") (pinfunction "2_2") (pintype "passive"))
      (node (ref "R30") (pin "2") (pinfunction "2_2") (pintype "passive"))
      (node (ref "R33") (pin "2") (pinfunction "2_2") (pintype "passive"))
      (node (ref "R36") (pin "2") (pinfunction "2_2") (pintype "passive"))
      (node (ref "R39") (pin "2") (pinfunction "2_2") (pintype "passive"))
      (node (ref "R42") (pin "2") (pinfunction "2_2") (pintype "passive"))
      (node (ref "R45") (pin "2") (pinfunction "2_2") (pintype "passive"))
      (node (ref "R48") (pin "2") (pinfunction "2_2") (pintype "passive"))
      (node (ref "R51") (pin "2") (pinfunction "2_2") (pintype "passive"))
      (node (ref "R54") (pin "2") (pinfunction "2_2") (pintype "passive"))
      (node (ref "R57") (pin "2") (pinfunction "2_2") (pintype "passive"))
      (node (ref "R6") (pin "2") (pinfunction "2_2") (pintype "passive"))
      (node (ref "R60") (pin "2") (pinfunction "2_2") (pintype "passive"))
      (node (ref "R63") (pin "2") (pinfunction "2_2") (pintype "passive"))
      (node (ref "R9") (pin "2") (pinfunction "2_2") (pintype "passive"))
    )
    (net (code "4") (name "/LED_G") (class "Default")
      (node (ref "R67") (pin "1") (pinfunction "1_1") (pintype "passive"))
      (node (ref "U1") (pin "4") (pinfunction "IO12_4") (pintype "passive"))
    )
    (net (code "5") (name "/LED_GK") (class "Default")
      (node (ref "Q3") (pin "4") (pinfunction "D_4") (pintype "passive"))
      (node (ref "R11") (pin "2") (pinfunction "2_2") (pintype "passive"))
      (node (ref "R14") (pin "2") (pinfunction "2_2") (pintype "passive"))
      (node (ref "R17") (pin "2") (pinfunction "2_2") (pintype "passive"))
      (node (ref "R2") (pin "2") (pinfunction "2_2") (pintype "passive"))
      (node (ref "R20") (pin "2") (pinfunction "2_2") (pintype "passive"))
      (node (ref "R23") (pin "2") (pinfunction "2_2") (pintype "passive"))
      (node (ref "R26") (pin "2") (pinfunction "2_2") (pintype "passive"))
      (node (ref "R29") (pin "2") (pinfunction "2_2") (pintype "passive"))
      (node (ref "R32") (pin "2") (pinfunction "2_2") (pintype "passive"))
      (node (ref "R35") (pin "2") (pinfunction "2_2") (pintype "passive"))
      (node (ref "R38") (pin "2") (pinfunction "2_2") (pintype "passive"))
      (node (ref "R41") (pin "2") (pinfunction "2_2") (pintype "passive"))
      (node (ref "R44") (pin "2") (pinfunction "2_2") (pintype "passive"))
      (node (ref "R47") (pin "2") (pinfunction "2_2") (pintype "passive"))
      (node (ref "R5") (pin "2") (pinfunction "2_2") (pintype "passive"))
      (node (ref "R50") (pin "2") (pinfunction "2_2") (pintype "passive"))
      (node (ref "R53") (pin "2") (pinfunction "2_2") (pintype "passive"))
      (node (ref "R56") (pin "2") (pinfunction "2_2") (pintype "passive"))
      (node (ref "R59") (pin "2") (pinfunction "2_2") (pintype "passive"))
      (node (ref "R62") (pin "2") (pinfunction "2_2") (pintype "passive"))
      (node (ref "R8") (pin "2") (pinfunction "2_2") (pintype "passive"))
    )
    (net (code "6") (name "/LED_R") (class "Default")
      (node (ref "R64") (pin "1") (pinfunction "1_1") (pintype "passive"))
      (node (ref "U1") (pin "3") (pinfunction "IO14_3") (pintype "passive"))
    )
    (net (code "7") (name "/LED_RK") (class "Default")
      (node (ref "Q1") (pin "4") (pinfunction "D_4") (pintype "passive"))
      (node (ref "R1") (pin "2") (pinfunction "2_2") (pintype "passive"))
      (node (ref "R10") (pin "2") (pinfunction "2_2") (pintype "passive"))
      (node (ref "R13") (pin "2") (pinfunction "2_2") (pintype "passive"))
      (node (ref "R16") (pin "2") (pinfunction "2_2") (pintype "passive"))
      (node (ref "R19") (pin "2") (pinfunction "2_2") (pintype "passive"))
      (node (ref "R22") (pin "2") (pinfunction "2_2") (pintype "passive"))
      (node (ref "R25") (pin "2") (pinfunction "2_2") (pintype "passive"))
      (node (ref "R28") (pin "2") (pinfunction "2_2") (pintype "passive"))
      (node (ref "R31") (pin "2") (pinfunction "2_2") (pintype "passive"))
      (node (ref "R34") (pin "2") (pinfunction "2_2") (pintype "passive"))
      (node (ref "R37") (pin "2") (pinfunction "2_2") (pintype "passive"))
      (node (ref "R4") (pin "2") (pinfunction "2_2") (pintype "passive"))
      (node (ref "R40") (pin "2") (pinfunction "2_2") (pintype "passive"))
      (node (ref "R43") (pin "2") (pinfunction "2_2") (pintype "passive"))
      (node (ref "R46") (pin "2") (pinfunction "2_2") (pintype "passive"))
      (node (ref "R49") (pin "2") (pinfunction "2_2") (pintype "passive"))
      (node (ref "R52") (pin "2") (pinfunction "2_2") (pintype "passive"))
      (node (ref "R55") (pin "2") (pinfunction "2_2") (pintype "passive"))
      (node (ref "R58") (pin "2") (pinfunction "2_2") (pintype "passive"))
      (node (ref "R61") (pin "2") (pinfunction "2_2") (pintype "passive"))
      (node (ref "R7") (pin "2") (pinfunction "2_2") (pintype "passive"))
    )
    (net (code "8") (name "/RST") (class "Default")
      (node (ref "J2") (pin "3") (pinfunction "3_3") (pintype "passive"))
      (node (ref "R68") (pin "2") (pinfunction "2_2") (pintype "passive"))
      (node (ref "U1") (pin "15") (pinfunction "RST_15") (pintype "passive"))
    )
    (net (code "9") (name "/RX") (class "Default")
      (node (ref "J2") (pin "2") (pinfunction "2_2") (pintype "passive"))
      (node (ref "U1") (pin "11") (pinfunction "RXD_11") (pintype "passive"))
    )
    (net (code "10") (name "/TX") (class "Default")
      (node (ref "J2") (pin "1") (pinfunction "1_1") (pintype "passive"))
      (node (ref "U1") (pin "12") (pinfunction "TXD_12") (pintype "passive"))
    )
    (net (code "11") (name "3V3") (class "Default")
      (node (ref "C2") (pin "2") (pinfunction "2_2") (pintype "passive"))
      (node (ref "J6") (pin "2") (pinfunction "2_2") (pintype "passive"))
      (node (ref "R66") (pin "2") (pinfunction "2_2") (pintype "passive"))
      (node (ref "R68") (pin "1") (pinfunction "1_1") (pintype "passive"))
      (node (ref "U1") (pin "1") (pinfunction "3V3_1") (pintype "passive"))
      (node (ref "U1") (pin "2") (pinfunction "EN_2") (pintype "passive"))
      (node (ref "U1") (pin "7") (pinfunction "IO2_7") (pintype "passive"))
      (node (ref "U2") (pin "2") (pinfunction "OUT_2") (pintype "passive"))
      (node (ref "U2") (pin "4") (pinfunction "OUT_4") (pintype "passive"))
    )
    (net (code "12") (name "5V") (class "Default")
      (node (ref "C1") (pin "2") (pinfunction "2_2") (pintype "passive"))
      (node (ref "D1") (pin "1") (pinfunction "BA_1") (pintype "passive"))
      (node (ref "D1") (pin "3") (pinfunction "GA_3") (pintype "passive"))
      (node (ref "D1") (pin "5") (pinfunction "RA_5") (pintype "passive"))
      (node (ref "D10") (pin "1") (pinfunction "BA_1") (pintype "passive"))
      (node (ref "D10") (pin "3") (pinfunction "GA_3") (pintype "passive"))
      (node (ref "D10") (pin "5") (pinfunction "RA_5") (pintype "passive"))
      (node (ref "D11") (pin "1") (pinfunction "BA_1") (pintype "passive"))
      (node (ref "D11") (pin "3") (pinfunction "GA_3") (pintype "passive"))
      (node (ref "D11") (pin "5") (pinfunction "RA_5") (pintype "passive"))
      (node (ref "D12") (pin "1") (pinfunction "BA_1") (pintype "passive"))
      (node (ref "D12") (pin "3") (pinfunction "GA_3") (pintype "passive"))
      (node (ref "D12") (pin "5") (pinfunction "RA_5") (pintype "passive"))
      (node (ref "D13") (pin "1") (pinfunction "BA_1") (pintype "passive"))
      (node (ref "D13") (pin "3") (pinfunction "GA_3") (pintype "passive"))
      (node (ref "D13") (pin "5") (pinfunction "RA_5") (pintype "passive"))
      (node (ref "D14") (pin "1") (pinfunction "BA_1") (pintype "passive"))
      (node (ref "D14") (pin "3") (pinfunction "GA_3") (pintype "passive"))
      (node (ref "D14") (pin "5") (pinfunction "RA_5") (pintype "passive"))
      (node (ref "D15") (pin "1") (pinfunction "BA_1") (pintype "passive"))
      (node (ref "D15") (pin "3") (pinfunction "GA_3") (pintype "passive"))
      (node (ref "D15") (pin "5") (pinfunction "RA_5") (pintype "passive"))
      (node (ref "D16") (pin "1") (pinfunction "BA_1") (pintype "passive"))
      (node (ref "D16") (pin "3") (pinfunction "GA_3") (pintype "passive"))
      (node (ref "D16") (pin "5") (pinfunction "RA_5") (pintype "passive"))
      (node (ref "D17") (pin "1") (pinfunction "BA_1") (pintype "passive"))
      (node (ref "D17") (pin "3") (pinfunction "GA_3") (pintype "passive"))
      (node (ref "D17") (pin "5") (pinfunction "RA_5") (pintype "passive"))
      (node (ref "D18") (pin "1") (pinfunction "BA_1") (pintype "passive"))
      (node (ref "D18") (pin "3") (pinfunction "GA_3") (pintype "passive"))
      (node (ref "D18") (pin "5") (pinfunction "RA_5") (pintype "passive"))
      (node (ref "D19") (pin "1") (pinfunction "BA_1") (pintype "passive"))
      (node (ref "D19") (pin "3") (pinfunction "GA_3") (pintype "passive"))
      (node (ref "D19") (pin "5") (pinfunction "RA_5") (pintype "passive"))
      (node (ref "D2") (pin "1") (pinfunction "BA_1") (pintype "passive"))
      (node (ref "D2") (pin "3") (pinfunction "GA_3") (pintype "passive"))
      (node (ref "D2") (pin "5") (pinfunction "RA_5") (pintype "passive"))
      (node (ref "D20") (pin "1") (pinfunction "BA_1") (pintype "passive"))
      (node (ref "D20") (pin "3") (pinfunction "GA_3") (pintype "passive"))
      (node (ref "D20") (pin "5") (pinfunction "RA_5") (pintype "passive"))
      (node (ref "D21") (pin "1") (pinfunction "BA_1") (pintype "passive"))
      (node (ref "D21") (pin "3") (pinfunction "GA_3") (pintype "passive"))
      (node (ref "D21") (pin "5") (pinfunction "RA_5") (pintype "passive"))
      (node (ref "D3") (pin "1") (pinfunction "BA_1") (pintype "passive"))
      (node (ref "D3") (pin "3") (pinfunction "GA_3") (pintype "passive"))
      (node (ref "D3") (pin "5") (pinfunction "RA_5") (pintype "passive"))
      (node (ref "D4") (pin "1") (pinfunction "BA_1") (pintype "passive"))
      (node (ref "D4") (pin "3") (pinfunction "GA_3") (pintype "passive"))
      (node (ref "D4") (pin "5") (pinfunction "RA_5") (pintype "passive"))
      (node (ref "D5") (pin "1") (pinfunction "BA_1") (pintype "passive"))
      (node (ref "D5") (pin "3") (pinfunction "GA_3") (pintype "passive"))
      (node (ref "D5") (pin "5") (pinfunction "RA_5") (pintype "passive"))
      (node (ref "D6") (pin "1") (pinfunction "BA_1") (pintype "passive"))
      (node (ref "D6") (pin "3") (pinfunction "GA_3") (pintype "passive"))
      (node (ref "D6") (pin "5") (pinfunction "RA_5") (pintype "passive"))
      (node (ref "D7") (pin "1") (pinfunction "BA_1") (pintype "passive"))
      (node (ref "D7") (pin "3") (pinfunction "GA_3") (pintype "passive"))
      (node (ref "D7") (pin "5") (pinfunction "RA_5") (pintype "passive"))
      (node (ref "D8") (pin "1") (pinfunction "BA_1") (pintype "passive"))
      (node (ref "D8") (pin "3") (pinfunction "GA_3") (pintype "passive"))
      (node (ref "D8") (pin "5") (pinfunction "RA_5") (pintype "passive"))
      (node (ref "D9") (pin "1") (pinfunction "BA_1") (pintype "passive"))
      (node (ref "D9") (pin "3") (pinfunction "GA_3") (pintype "passive"))
      (node (ref "D9") (pin "5") (pinfunction "RA_5") (pintype "passive"))
      (node (ref "J1") (pin "1") (pinfunction "5V_1") (pintype "power_in"))
      (node (ref "U2") (pin "3") (pinfunction "IN_3") (pintype "passive"))
    )
    (net (code "13") (name "GND") (class "Default")
      (node (ref "C1") (pin "1") (pinfunction "1_1") (pintype "passive"))
      (node (ref "C2") (pin "1") (pinfunction "1_1") (pintype "passive"))
      (node (ref "J1") (pin "0") (pinfunction "SH_0") (pintype "passive"))
      (node (ref "J1") (pin "5") (pinfunction "GND_5") (pintype "power_in"))
      (node (ref "J2") (pin "4") (pinfunction "4_4") (pintype "passive"))
      (node (ref "J3") (pin "0") (pinfunction "PIN_0") (pintype "passive"))
      (node (ref "J4") (pin "0") (pinfunction "PIN_0") (pintype "passive"))
      (node (ref "J5") (pin "0") (pinfunction "PIN_0") (pintype "passive"))
      (node (ref "J6") (pin "3") (pinfunction "3_3") (pintype "passive"))
      (node (ref "Q1") (pin "3") (pinfunction "S_3") (pintype "passive"))
      (node (ref "Q2") (pin "3") (pinfunction "S_3") (pintype "passive"))
      (node (ref "Q3") (pin "3") (pinfunction "S_3") (pintype "passive"))
      (node (ref "SW1") (pin "3") (pinfunction "3_3") (pintype "passive"))
      (node (ref "SW1") (pin "4") (pinfunction "4_4") (pintype "passive"))
      (node (ref "U1") (pin "13") (pinfunction "GND_13") (pintype "passive"))
      (node (ref "U1") (pin "18") (pinfunction "GND_18") (pintype "passive"))
      (node (ref "U1") (pin "19") (pinfunction "GND_19") (pintype "passive"))
      (node (ref "U1") (pin "6") (pinfunction "IO15_6") (pintype "passive"))
      (node (ref "U1") (pin "9") (pinfunction "GND_9") (pintype "passive"))
      (node (ref "U2") (pin "1") (pinfunction "GND_1") (pintype "passive"))
    )
    (net (code "14") (name "Net-(D1-BK)") (class "Default")
      (node (ref "D1") (pin "2") (pinfunction "BK_2") (pintype "passive"))
      (node (ref "R3") (pin "1") (pinfunction "1_1") (pintype "passive"))
    )
    (net (code "15") (name "Net-(D1-GK)") (class "Default")
      (node (ref "D1") (pin "4") (pinfunction "GK_4") (pintype "passive"))
      (node (ref "R2") (pin "1") (pinfunction "1_1") (pintype "passive"))
    )
    (net (code "16") (name "Net-(D1-RK)") (class "Default")
      (node (ref "D1") (pin "6") (pinfunction "RK_6") (pintype "passive"))
      (node (ref "R1") (pin "1") (pinfunction "1_1") (pintype "passive"))
    )
    (net (code "17") (name "Net-(D2-BK)") (class "Default")
      (node (ref "D2") (pin "2") (pinfunction "BK_2") (pintype "passive"))
      (node (ref "R6") (pin "1") (pinfunction "1_1") (pintype "passive"))
    )
    (net (code "18") (name "Net-(D2-GK)") (class "Default")
      (node (ref "D2") (pin "4") (pinfunction "GK_4") (pintype "passive"))
      (node (ref "R5") (pin "1") (pinfunction "1_1") (pintype "passive"))
    )
    (net (code "19") (name "Net-(D2-RK)") (class "Default")
      (node (ref "D2") (pin "6") (pinfunction "RK_6") (pintype "passive"))
      (node (ref "R4") (pin "1") (pinfunction "1_1") (pintype "passive"))
    )
    (net (code "20") (name "Net-(D3-BK)") (class "Default")
      (node (ref "D3") (pin "2") (pinfunction "BK_2") (pintype "passive"))
      (node (ref "R9") (pin "1") (pinfunction "1_1") (pintype "passive"))
    )
    (net (code "21") (name "Net-(D3-GK)") (class "Default")
      (node (ref "D3") (pin "4") (pinfunction "GK_4") (pintype "passive"))
      (node (ref "R8") (pin "1") (pinfunction "1_1") (pintype "passive"))
    )
    (net (code "22") (name "Net-(D3-RK)") (class "Default")
      (node (ref "D3") (pin "6") (pinfunction "RK_6") (pintype "passive"))
      (node (ref "R7") (pin "1") (pinfunction "1_1") (pintype "passive"))
    )
    (net (code "23") (name "Net-(D4-BK)") (class "Default")
      (node (ref "D4") (pin "2") (pinfunction "BK_2") (pintype "passive"))
      (node (ref "R12") (pin "1") (pinfunction "1_1") (pintype "passive"))
    )
    (net (code "24") (name "Net-(D4-GK)") (class "Default")
      (node (ref "D4") (pin "4") (pinfunction "GK_4") (pintype "passive"))
      (node (ref "R11") (pin "1") (pinfunction "1_1") (pintype "passive"))
    )
    (net (code "25") (name "Net-(D4-RK)") (class "Default")
      (node (ref "D4") (pin "6") (pinfunction "RK_6") (pintype "passive"))
      (node (ref "R10") (pin "1") (pinfunction "1_1") (pintype "passive"))
    )
    (net (code "26") (name "Net-(D5-BK)") (class "Default")
      (node (ref "D5") (pin "2") (pinfunction "BK_2") (pintype "passive"))
      (node (ref "R15") (pin "1") (pinfunction "1_1") (pintype "passive"))
    )
    (net (code "27") (name "Net-(D5-GK)") (class "Default")
      (node (ref "D5") (pin "4") (pinfunction "GK_4") (pintype "passive"))
      (node (ref "R14") (pin "1") (pinfunction "1_1") (pintype "passive"))
    )
    (net (code "28") (name "Net-(D5-RK)") (class "Default")
      (node (ref "D5") (pin "6") (pinfunction "RK_6") (pintype "passive"))
      (node (ref "R13") (pin "1") (pinfunction "1_1") (pintype "passive"))
    )
    (net (code "29") (name "Net-(D6-BK)") (class "Default")
      (node (ref "D6") (pin "2") (pinfunction "BK_2") (pintype "passive"))
      (node (ref "R18") (pin "1") (pinfunction "1_1") (pintype "passive"))
    )
    (net (code "30") (name "Net-(D6-GK)") (class "Default")
      (node (ref "D6") (pin "4") (pinfunction "GK_4") (pintype "passive"))
      (node (ref "R17") (pin "1") (pinfunction "1_1") (pintype "passive"))
    )
    (net (code "31") (name "Net-(D6-RK)") (class "Default")
      (node (ref "D6") (pin "6") (pinfunction "RK_6") (pintype "passive"))
      (node (ref "R16") (pin "1") (pinfunction "1_1") (pintype "passive"))
    )
    (net (code "32") (name "Net-(D7-BK)") (class "Default")
      (node (ref "D7") (pin "2") (pinfunction "BK_2") (pintype "passive"))
      (node (ref "R21") (pin "1") (pinfunction "1_1") (pintype "passive"))
    )
    (net (code "33") (name "Net-(D7-GK)") (class "Default")
      (node (ref "D7") (pin "4") (pinfunction "GK_4") (pintype "passive"))
      (node (ref "R20") (pin "1") (pinfunction "1_1") (pintype "passive"))
    )
    (net (code "34") (name "Net-(D7-RK)") (class "Default")
      (node (ref "D7") (pin "6") (pinfunction "RK_6") (pintype "passive"))
      (node (ref "R19") (pin "1") (pinfunction "1_1") (pintype "passive"))
    )
    (net (code "35") (name "Net-(D8-BK)") (class "Default")
      (node (ref "D8") (pin "2") (pinfunction "BK_2") (pintype "passive"))
      (node (ref "R24") (pin "1") (pinfunction "1_1") (pintype "passive"))
    )
    (net (code "36") (name "Net-(D8-GK)") (class "Default")
      (node (ref "D8") (pin "4") (pinfunction "GK_4") (pintype "passive"))
      (node (ref "R23") (pin "1") (pinfunction "1_1") (pintype "passive"))
    )
    (net (code "37") (name "Net-(D8-RK)") (class "Default")
      (node (ref "D8") (pin "6") (pinfunction "RK_6") (pintype "passive"))
      (node (ref "R22") (pin "1") (pinfunction "1_1") (pintype "passive"))
    )
    (net (code "38") (name "Net-(D9-BK)") (class "Default")
      (node (ref "D9") (pin "2") (pinfunction "BK_2") (pintype "passive"))
      (node (ref "R27") (pin "1") (pinfunction "1_1") (pintype "passive"))
    )
    (net (code "39") (name "Net-(D9-GK)") (class "Default")
      (node (ref "D9") (pin "4") (pinfunction "GK_4") (pintype "passive"))
      (node (ref "R26") (pin "1") (pinfunction "1_1") (pintype "passive"))
    )
    (net (code "40") (name "Net-(D9-RK)") (class "Default")
      (node (ref "D9") (pin "6") (pinfunction "RK_6") (pintype "passive"))
      (node (ref "R25") (pin "1") (pinfunction "1_1") (pintype "passive"))
    )
    (net (code "41") (name "Net-(D10-BK)") (class "Default")
      (node (ref "D10") (pin "2") (pinfunction "BK_2") (pintype "passive"))
      (node (ref "R30") (pin "1") (pinfunction "1_1") (pintype "passive"))
    )
    (net (code "42") (name "Net-(D10-GK)") (class "Default")
      (node (ref "D10") (pin "4") (pinfunction "GK_4") (pintype "passive"))
      (node (ref "R29") (pin "1") (pinfunction "1_1") (pintype "passive"))
    )
    (net (code "43") (name "Net-(D10-RK)") (class "Default")
      (node (ref "D10") (pin "6") (pinfunction "RK_6") (pintype "passive"))
      (node (ref "R28") (pin "1") (pinfunction "1_1") (pintype "passive"))
    )
    (net (code "44") (name "Net-(D11-BK)") (class "Default")
      (node (ref "D11") (pin "2") (pinfunction "BK_2") (pintype "passive"))
      (node (ref "R33") (pin "1") (pinfunction "1_1") (pintype "passive"))
    )
    (net (code "45") (name "Net-(D11-GK)") (class "Default")
      (node (ref "D11") (pin "4") (pinfunction "GK_4") (pintype "passive"))
      (node (ref "R32") (pin "1") (pinfunction "1_1") (pintype "passive"))
    )
    (net (code "46") (name "Net-(D11-RK)") (class "Default")
      (node (ref "D11") (pin "6") (pinfunction "RK_6") (pintype "passive"))
      (node (ref "R31") (pin "1") (pinfunction "1_1") (pintype "passive"))
    )
    (net (code "47") (name "Net-(D12-BK)") (class "Default")
      (node (ref "D12") (pin "2") (pinfunction "BK_2") (pintype "passive"))
      (node (ref "R36") (pin "1") (pinfunction "1_1") (pintype "passive"))
    )
    (net (code "48") (name "Net-(D12-GK)") (class "Default")
      (node (ref "D12") (pin "4") (pinfunction "GK_4") (pintype "passive"))
      (node (ref "R35") (pin "1") (pinfunction "1_1") (pintype "passive"))
    )
    (net (code "49") (name "Net-(D12-RK)") (class "Default")
      (node (ref "D12") (pin "6") (pinfunction "RK_6") (pintype "passive"))
      (node (ref "R34") (pin "1") (pinfunction "1_1") (pintype "passive"))
    )
    (net (code "50") (name "Net-(D13-BK)") (class "Default")
      (node (ref "D13") (pin "2") (pinfunction "BK_2") (pintype "passive"))
      (node (ref "R39") (pin "1") (pinfunction "1_1") (pintype "passive"))
    )
    (net (code "51") (name "Net-(D13-GK)") (class "Default")
      (node (ref "D13") (pin "4") (pinfunction "GK_4") (pintype "passive"))
      (node (ref "R38") (pin "1") (pinfunction "1_1") (pintype "passive"))
    )
    (net (code "52") (name "Net-(D13-RK)") (class "Default")
      (node (ref "D13") (pin "6") (pinfunction "RK_6") (pintype "passive"))
      (node (ref "R37") (pin "1") (pinfunction "1_1") (pintype "passive"))
    )
    (net (code "53") (name "Net-(D14-BK)") (class "Default")
      (node (ref "D14") (pin "2") (pinfunction "BK_2") (pintype "passive"))
      (node (ref "R42") (pin "1") (pinfunction "1_1") (pintype "passive"))
    )
    (net (code "54") (name "Net-(D14-GK)") (class "Default")
      (node (ref "D14") (pin "4") (pinfunction "GK_4") (pintype "passive"))
      (node (ref "R41") (pin "1") (pinfunction "1_1") (pintype "passive"))
    )
    (net (code "55") (name "Net-(D14-RK)") (class "Default")
      (node (ref "D14") (pin "6") (pinfunction "RK_6") (pintype "passive"))
      (node (ref "R40") (pin "1") (pinfunction "1_1") (pintype "passive"))
    )
    (net (code "56") (name "Net-(D15-BK)") (class "Default")
      (node (ref "D15") (pin "2") (pinfunction "BK_2") (pintype "passive"))
      (node (ref "R45") (pin "1") (pinfunction "1_1") (pintype "passive"))
    )
    (net (code "57") (name "Net-(D15-GK)") (class "Default")
      (node (ref "D15") (pin "4") (pinfunction "GK_4") (pintype "passive"))
      (node (ref "R44") (pin "1") (pinfunction "1_1") (pintype "passive"))
    )
    (net (code "58") (name "Net-(D15-RK)") (class "Default")
      (node (ref "D15") (pin "6") (pinfunction "RK_6") (pintype "passive"))
      (node (ref "R43") (pin "1") (pinfunction "1_1") (pintype "passive"))
    )
    (net (code "59") (name "Net-(D16-BK)") (class "Default")
      (node (ref "D16") (pin "2") (pinfunction "BK_2") (pintype "passive"))
      (node (ref "R48") (pin "1") (pinfunction "1_1") (pintype "passive"))
    )
    (net (code "60") (name "Net-(D16-GK)") (class "Default")
      (node (ref "D16") (pin "4") (pinfunction "GK_4") (pintype "passive"))
      (node (ref "R47") (pin "1") (pinfunction "1_1") (pintype "passive"))
    )
    (net (code "61") (name "Net-(D16-RK)") (class "Default")
      (node (ref "D16") (pin "6") (pinfunction "RK_6") (pintype "passive"))
      (node (ref "R46") (pin "1") (pinfunction "1_1") (pintype "passive"))
    )
    (net (code "62") (name "Net-(D17-BK)") (class "Default")
      (node (ref "D17") (pin "2") (pinfunction "BK_2") (pintype "passive"))
      (node (ref "R51") (pin "1") (pinfunction "1_1") (pintype "passive"))
    )
    (net (code "63") (name "Net-(D17-GK)") (class "Default")
      (node (ref "D17") (pin "4") (pinfunction "GK_4") (pintype "passive"))
      (node (ref "R50") (pin "1") (pinfunction "1_1") (pintype "passive"))
    )
    (net (code "64") (name "Net-(D17-RK)") (class "Default")
      (node (ref "D17") (pin "6") (pinfunction "RK_6") (pintype "passive"))
      (node (ref "R49") (pin "1") (pinfunction "1_1") (pintype "passive"))
    )
    (net (code "65") (name "Net-(D18-BK)") (class "Default")
      (node (ref "D18") (pin "2") (pinfunction "BK_2") (pintype "passive"))
      (node (ref "R54") (pin "1") (pinfunction "1_1") (pintype "passive"))
    )
    (net (code "66") (name "Net-(D18-GK)") (class "Default")
      (node (ref "D18") (pin "4") (pinfunction "GK_4") (pintype "passive"))
      (node (ref "R53") (pin "1") (pinfunction "1_1") (pintype "passive"))
    )
    (net (code "67") (name "Net-(D18-RK)") (class "Default")
      (node (ref "D18") (pin "6") (pinfunction "RK_6") (pintype "passive"))
      (node (ref "R52") (pin "1") (pinfunction "1_1") (pintype "passive"))
    )
    (net (code "68") (name "Net-(D19-BK)") (class "Default")
      (node (ref "D19") (pin "2") (pinfunction "BK_2") (pintype "passive"))
      (node (ref "R57") (pin "1") (pinfunction "1_1") (pintype "passive"))
    )
    (net (code "69") (name "Net-(D19-GK)") (class "Default")
      (node (ref "D19") (pin "4") (pinfunction "GK_4") (pintype "passive"))
      (node (ref "R56") (pin "1") (pinfunction "1_1") (pintype "passive"))
    )
    (net (code "70") (name "Net-(D19-RK)") (class "Default")
      (node (ref "D19") (pin "6") (pinfunction "RK_6") (pintype "passive"))
      (node (ref "R55") (pin "1") (pinfunction "1_1") (pintype "passive"))
    )
    (net (code "71") (name "Net-(D20-BK)") (class "Default")
      (node (ref "D20") (pin "2") (pinfunction "BK_2") (pintype "passive"))
      (node (ref "R60") (pin "1") (pinfunction "1_1") (pintype "passive"))
    )
    (net (code "72") (name "Net-(D20-GK)") (class "Default")
      (node (ref "D20") (pin "4") (pinfunction "GK_4") (pintype "passive"))
      (node (ref "R59") (pin "1") (pinfunction "1_1") (pintype "passive"))
    )
    (net (code "73") (name "Net-(D20-RK)") (class "Default")
      (node (ref "D20") (pin "6") (pinfunction "RK_6") (pintype "passive"))
      (node (ref "R58") (pin "1") (pinfunction "1_1") (pintype "passive"))
    )
    (net (code "74") (name "Net-(D21-BK)") (class "Default")
      (node (ref "D21") (pin "2") (pinfunction "BK_2") (pintype "passive"))
      (node (ref "R63") (pin "1") (pinfunction "1_1") (pintype "passive"))
    )
    (net (code "75") (name "Net-(D21-GK)") (class "Default")
      (node (ref "D21") (pin "4") (pinfunction "GK_4") (pintype "passive"))
      (node (ref "R62") (pin "1") (pinfunction "1_1") (pintype "passive"))
    )
    (net (code "76") (name "Net-(D21-RK)") (class "Default")
      (node (ref "D21") (pin "6") (pinfunction "RK_6") (pintype "passive"))
      (node (ref "R61") (pin "1") (pinfunction "1_1") (pintype "passive"))
    )
    (net (code "77") (name "Net-(Q1-G)") (class "Default")
      (node (ref "Q1") (pin "1") (pinfunction "G_1") (pintype "passive"))
      (node (ref "R64") (pin "2") (pinfunction "2_2") (pintype "passive"))
    )
    (net (code "78") (name "Net-(Q2-G)") (class "Default")
      (node (ref "Q2") (pin "1") (pinfunction "G_1") (pintype "passive"))
      (node (ref "R65") (pin "2") (pinfunction "2_2") (pintype "passive"))
    )
    (net (code "79") (name "Net-(Q3-G)") (class "Default")
      (node (ref "Q3") (pin "1") (pinfunction "G_1") (pintype "passive"))
      (node (ref "R67") (pin "2") (pinfunction "2_2") (pintype "passive"))
    )
    (net (code "80") (name "Net-(U1-IO0)") (class "Default")
      (node (ref "R66") (pin "1") (pinfunction "1_1") (pintype "passive"))
      (node (ref "SW1") (pin "1") (pinfunction "1_1") (pintype "passive"))
      (node (ref "SW1") (pin "2") (pinfunction "2_2") (pintype "passive"))
      (node (ref "U1") (pin "8") (pinfunction "IO0_8") (pintype "passive"))
    )
    (net (code "81") (name "unconnected-(J1-D+-Pad3)") (class "Default")
      (node (ref "J1") (pin "3") (pinfunction "D+_3") (pintype "bidirectional+no_connect"))
    )
    (net (code "82") (name "unconnected-(J1-D--Pad2)") (class "Default")
      (node (ref "J1") (pin "2") (pinfunction "D-_2") (pintype "bidirectional+no_connect"))
    )
    (net (code "83") (name "unconnected-(J1-ID-Pad4)") (class "Default")
      (node (ref "J1") (pin "4") (pinfunction "ID_4") (pintype "passive+no_connect"))
    )
    (net (code "84") (name "unconnected-(U1-IO4-Pad10)") (class "Default")
      (node (ref "U1") (pin "10") (pinfunction "IO4_10") (pintype "passive+no_connect"))
    )
    (net (code "85") (name "unconnected-(U1-IO5-Pad14)") (class "Default")
      (node (ref "U1") (pin "14") (pinfunction "IO5_14") (pintype "passive+no_connect"))
    )
    (net (code "86") (name "unconnected-(U1-IO16-Pad17)") (class "Default")
      (node (ref "U1") (pin "17") (pinfunction "IO16_17") (pintype "passive+no_connect"))
    )
  )
)
